# TPS75501_3V3B.net
KiCad netlist of a schematic drawn in Altium Designer
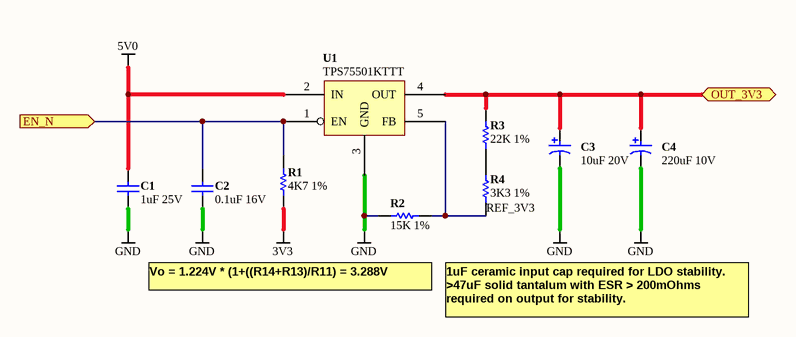
[diagram p0: TPS75501_3V3B.SchDoc]

(export (version "E")
  (design (tool "Eeschema 10.0.6"))
  (components
    (comp (ref "C1")
      (value "1uF 25V")
      (footprint "CAPC3216-STAR")
      (description "Capacitor, Ceramic, 1uF 10% 25V 1206 (3216) X7R")
      (fields (field (name "TOLERANCE") "10 %"))
      (libsource (lib "AltiumDesignLibrary") (part "CAP-NP"))
    )
    (comp (ref "C2")
      (value "0.1uF 16V")
      (footprint "CAPC1005-STAR")
      (description "Capacitor, Ceramic, 0.1uF 10% 16V 0402 (1005) X7R")
      (fields (field (name "TOLERANCE") "10 %"))
      (libsource (lib "AltiumDesignLibrary") (part "CAP-NP"))
    )
    (comp (ref "C3")
      (value "10uF 20V")
      (footprint "CAPC3528-STAR")
      (description "Capacitor, Tantalum, 10uF 10% 20V MCCT-B (3528)")
      (fields (field (name "TOLERANCE") "10 %"))
      (libsource (lib "AltiumDesignLibrary") (part "CAP-P"))
    )
    (comp (ref "C4")
      (value "220uF 10V")
      (footprint "CAPC7343-STAR")
      (description "Capacitor, Tantalum, 220uF 10% 10V MCCT-D (7343-31)")
      (fields (field (name "TOLERANCE") "10 %"))
      (libsource (lib "AltiumDesignLibrary") (part "CAP-P"))
    )
    (comp (ref "R1")
      (value "4K7 1%")
      (footprint "RESC1005-STAR")
      (description "Resistor, 4K7 1% 0402 (1005)")
      (fields (field (name "TOLERANCE") "1 %"))
      (libsource (lib "AltiumDesignLibrary") (part "RES"))
    )
    (comp (ref "R2")
      (value "15K 1%")
      (footprint "RESC1005-STAR")
      (description "Resistor, 15K 1% 0402 (1005)")
      (fields (field (name "TOLERANCE") "1 %"))
      (libsource (lib "AltiumDesignLibrary") (part "RES"))
    )
    (comp (ref "R3")
      (value "22K 1%")
      (footprint "RESC1005-STAR")
      (description "Resistor, 22K 1% 0402 (1005)")
      (fields (field (name "TOLERANCE") "1 %"))
      (libsource (lib "AltiumDesignLibrary") (part "RES"))
    )
    (comp (ref "R4")
      (value "3K3 1%")
      (footprint "RESC1005-STAR")
      (description "Resistor, 3K3 1% 0402 (1005)")
      (fields (field (name "TOLERANCE") "1 %"))
      (libsource (lib "AltiumDesignLibrary") (part "RES"))
    )
    (comp (ref "U1")
      (value "TPS75501KTTT")
      (footprint "TO-263")
      (description "TPS75501KTTT, 5A, Low Dropout, Adjustable, Linear Voltage Regulator, TO-263")
      (libsource (lib "AltiumDesignLibrary") (part "TPS75501"))
    )
  )
  (nets
    (net (code "1") (name "/EN_N") (class "Default")
      (node (ref "C2") (pin "1") (pinfunction "1_1") (pintype "passive"))
      (node (ref "R1") (pin "1") (pinfunction "1_1") (pintype "passive"))
      (node (ref "U1") (pin "1") (pinfunction "EN_1") (pintype "passive"))
    )
    (net (code "2") (name "/OUT_3V3") (class "Default")
      (node (ref "C3") (pin "1") (pinfunction "1_1") (pintype "passive"))
      (node (ref "C4") (pin "1") (pinfunction "1_1") (pintype "passive"))
      (node (ref "R3") (pin "2") (pinfunction "2_2") (pintype "passive"))
      (node (ref "U1") (pin "4") (pinfunction "OUT_4") (pintype "passive"))
    )
    (net (code "3") (name "/REF_3V3") (class "Default")
      (node (ref "R2") (pin "2") (pinfunction "2_2") (pintype "passive"))
      (node (ref "R4") (pin "1") (pinfunction "1_1") (pintype "passive"))
      (node (ref "U1") (pin "5") (pinfunction "FB_5") (pintype "passive"))
    )
    (net (code "4") (name "3V3") (class "Default")
      (node (ref "R1") (pin "2") (pinfunction "2_2") (pintype "passive"))
    )
    (net (code "5") (name "5V0") (class "Default")
      (node (ref "C1") (pin "1") (pinfunction "1_1") (pintype "passive"))
      (node (ref "U1") (pin "2") (pinfunction "IN_2") (pintype "passive"))
    )
    (net (code "6") (name "GND") (class "Default")
      (node (ref "C1") (pin "2") (pinfunction "2_2") (pintype "passive"))
      (node (ref "C2") (pin "2") (pinfunction "2_2") (pintype "passive"))
      (node (ref "C3") (pin "2") (pinfunction "2_2") (pintype "passive"))
      (node (ref "C4") (pin "2") (pinfunction "2_2") (pintype "passive"))
      (node (ref "R2") (pin "1") (pinfunction "1_1") (pintype "passive"))
      (node (ref "U1") (pin "3") (pinfunction "GND_3") (pintype "passive"))
    )
    (net (code "7") (name "Net-(R3-Pad1)") (class "Default")
      (node (ref "R3") (pin "1") (pinfunction "1_1") (pintype "passive"))
      (node (ref "R4") (pin "2") (pinfunction "2_2") (pintype "passive"))
    )
  )
)
